# Analog.net
KiCad netlist of a schematic drawn in Altium Designer
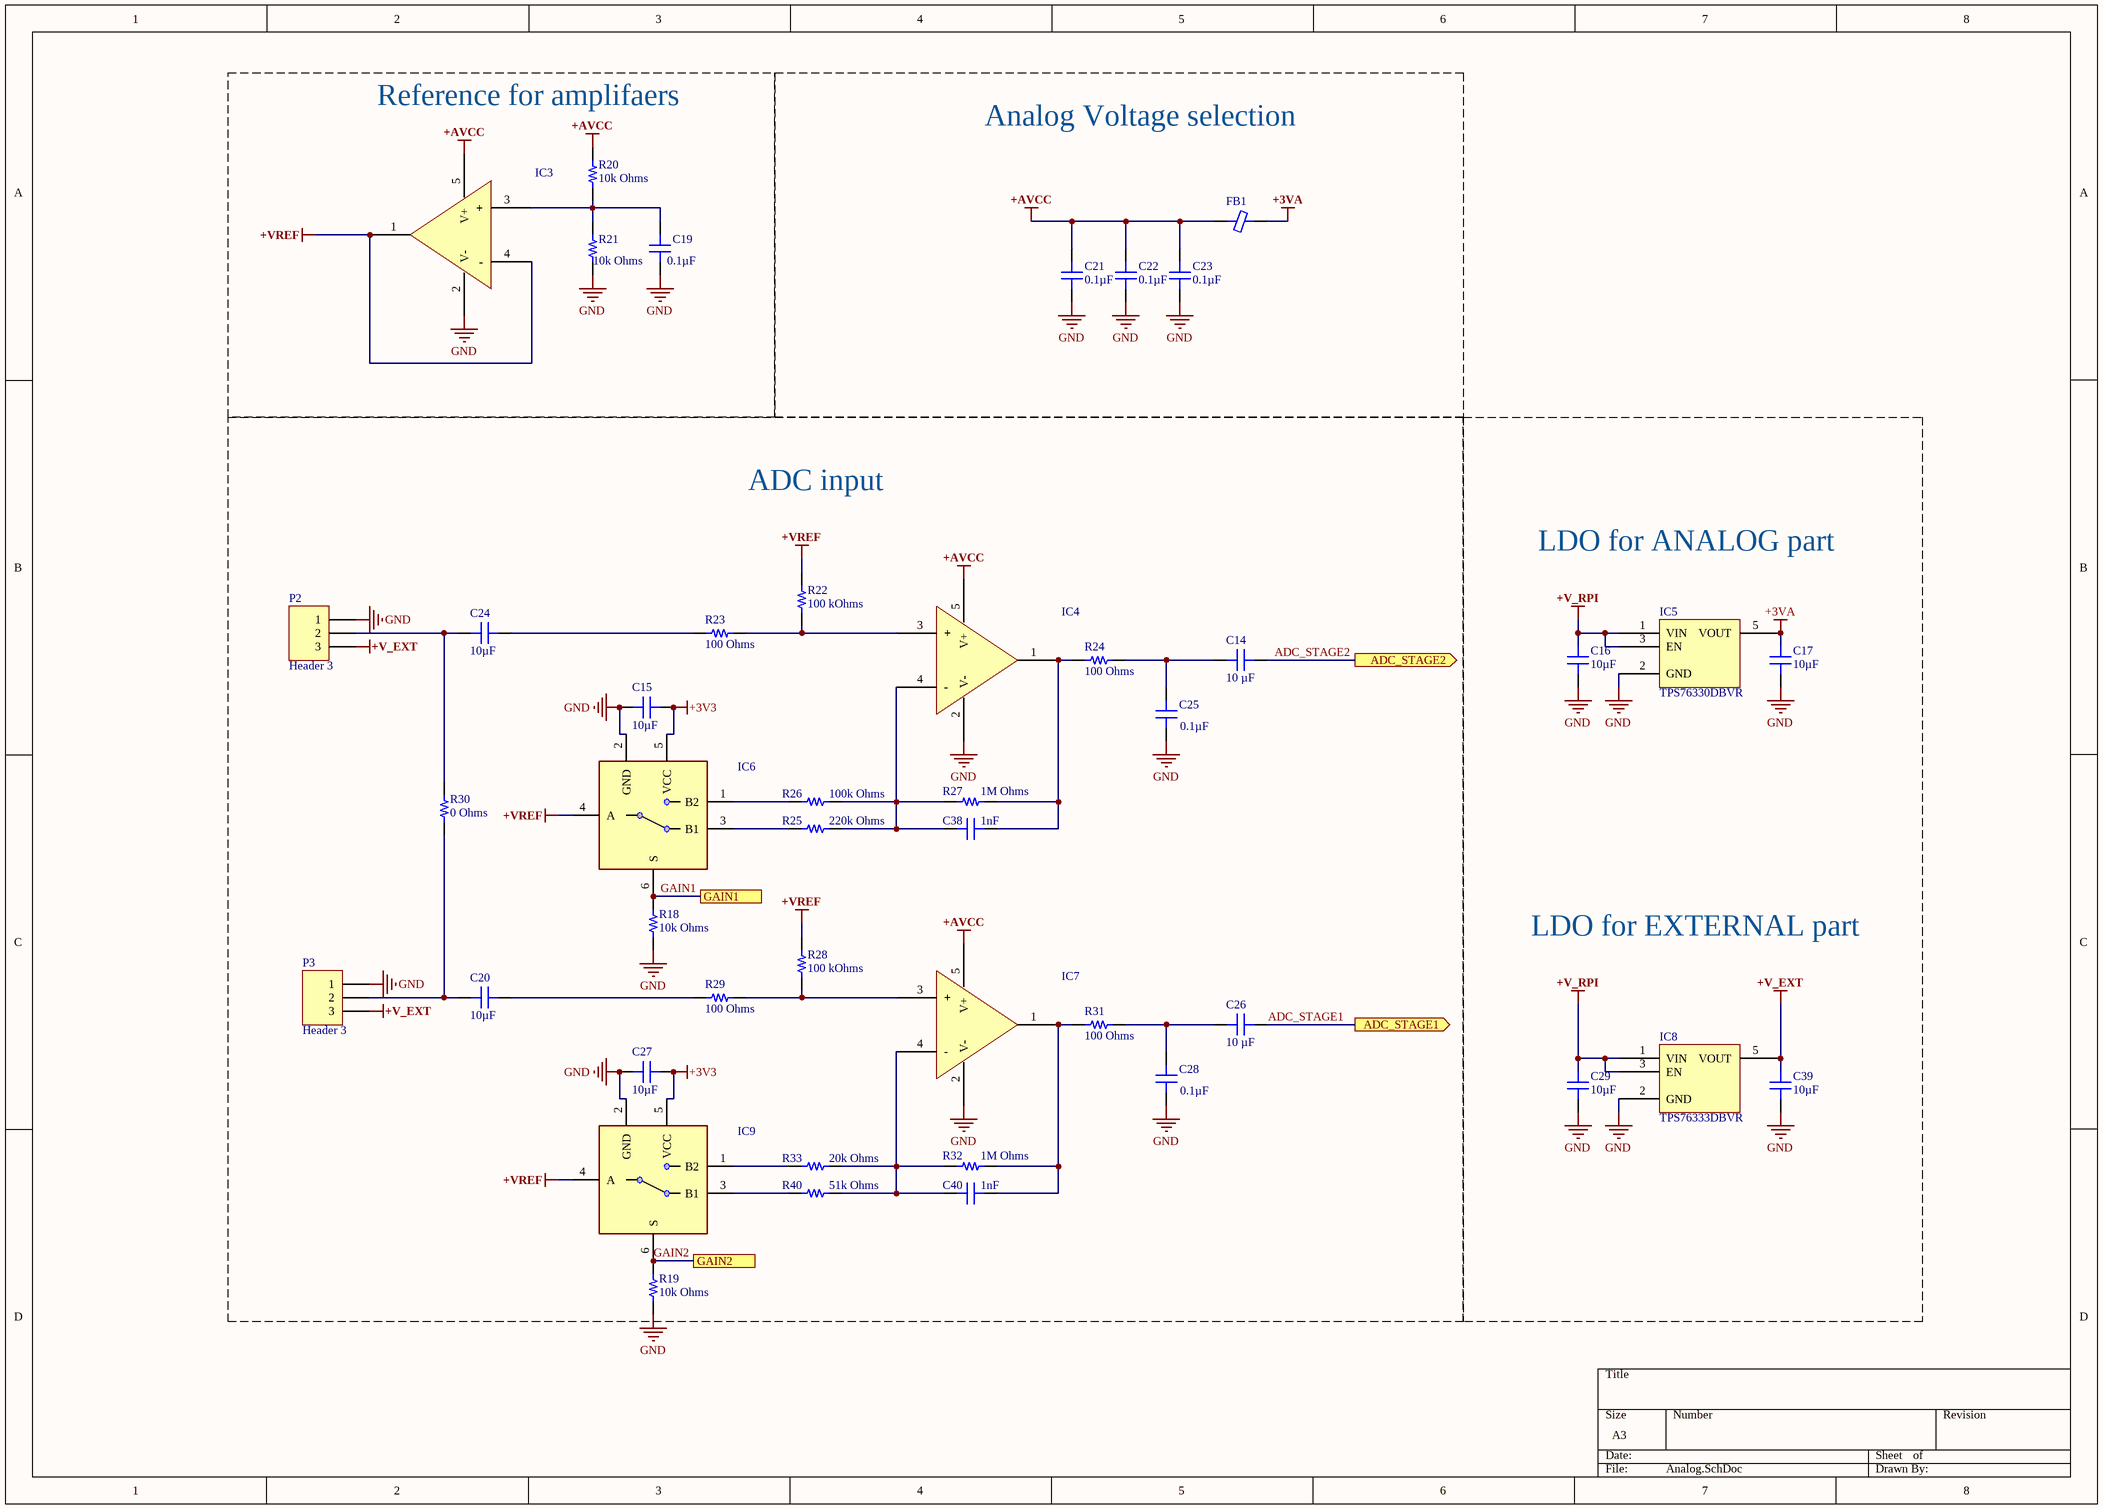
[diagram p0: Analog.SchDoc]

(export (version "E")
  (design (tool "Eeschema 10.0.6"))
  (components
    (comp (ref "C14")
      (value "10 µF")
      (footprint "CAP 0603_1608")
      (description "CAP CER 0.1UF 10V X7R 0603")
      (fields (field (name "PART NUMBER") "100X14W104MV4T"))
      (libsource (lib "Celestial Altium Library - altium_library") (part "Capacitor"))
    )
    (comp (ref "C15")
      (value "10µF")
      (footprint "CAP 0603_1608")
      (description "CAP CER 0.1UF 10V X7R 0603")
      (fields (field (name "PART NUMBER") "100X14W104MV4T"))
      (libsource (lib "Celestial Altium Library - altium_library") (part "Capacitor"))
    )
    (comp (ref "C16")
      (value "10µF")
      (footprint "CAP 0603_1608")
      (description "CAP CER 0.1UF 10V X7R 0603")
      (fields (field (name "PART NUMBER") "100X14W104MV4T"))
      (libsource (lib "Celestial Altium Library - altium_library") (part "Capacitor"))
    )
    (comp (ref "C17")
      (value "10µF")
      (footprint "CAP 0603_1608")
      (description "CAP CER 0.1UF 10V X7R 0603")
      (fields (field (name "PART NUMBER") "100X14W104MV4T"))
      (libsource (lib "Celestial Altium Library - altium_library") (part "Capacitor"))
    )
    (comp (ref "C19")
      (value "0.1µF")
      (footprint "CAP 0603_1608")
      (description "CAP CER 0.1UF 10V X7R 0603")
      (fields (field (name "PART NUMBER") "100X14W104MV4T"))
      (libsource (lib "Celestial Altium Library - altium_library") (part "Capacitor"))
    )
    (comp (ref "C20")
      (value "10µF")
      (footprint "CAP 0603_1608")
      (description "CAP CER 0.1UF 10V X7R 0603")
      (fields (field (name "PART NUMBER") "100X14W104MV4T"))
      (libsource (lib "Celestial Altium Library - altium_library") (part "Capacitor"))
    )
    (comp (ref "C21")
      (value "0.1µF")
      (footprint "CAP 0603_1608")
      (description "CAP CER 0.1UF 10V X7R 0603")
      (fields (field (name "PART NUMBER") "100X14W104MV4T"))
      (libsource (lib "Celestial Altium Library - altium_library") (part "Capacitor"))
    )
    (comp (ref "C22")
      (value "0.1µF")
      (footprint "CAP 0603_1608")
      (description "CAP CER 0.1UF 10V X7R 0603")
      (fields (field (name "PART NUMBER") "100X14W104MV4T"))
      (libsource (lib "Celestial Altium Library - altium_library") (part "Capacitor"))
    )
    (comp (ref "C23")
      (value "0.1µF")
      (footprint "CAP 0603_1608")
      (description "CAP CER 0.1UF 10V X7R 0603")
      (fields (field (name "PART NUMBER") "100X14W104MV4T"))
      (libsource (lib "Celestial Altium Library - altium_library") (part "Capacitor"))
    )
    (comp (ref "C24")
      (value "10µF")
      (footprint "CAP 0603_1608")
      (description "CAP CER 0.1UF 10V X7R 0603")
      (fields (field (name "PART NUMBER") "100X14W104MV4T"))
      (libsource (lib "Celestial Altium Library - altium_library") (part "Capacitor"))
    )
    (comp (ref "C25")
      (value "0.1µF")
      (footprint "CAP 0603_1608")
      (description "CAP CER 0.1UF 10V X7R 0603")
      (fields (field (name "PART NUMBER") "100X14W104MV4T"))
      (libsource (lib "Celestial Altium Library - altium_library") (part "Capacitor"))
    )
    (comp (ref "C26")
      (value "10 µF")
      (footprint "CAP 0603_1608")
      (description "CAP CER 0.1UF 10V X7R 0603")
      (fields (field (name "PART NUMBER") "100X14W104MV4T"))
      (libsource (lib "Celestial Altium Library - altium_library") (part "Capacitor"))
    )
    (comp (ref "C27")
      (value "10µF")
      (footprint "CAP 0603_1608")
      (description "CAP CER 0.1UF 10V X7R 0603")
      (fields (field (name "PART NUMBER") "100X14W104MV4T"))
      (libsource (lib "Celestial Altium Library - altium_library") (part "Capacitor"))
    )
    (comp (ref "C28")
      (value "0.1µF")
      (footprint "CAP 0603_1608")
      (description "CAP CER 0.1UF 10V X7R 0603")
      (fields (field (name "PART NUMBER") "100X14W104MV4T"))
      (libsource (lib "Celestial Altium Library - altium_library") (part "Capacitor"))
    )
    (comp (ref "C29")
      (value "10µF")
      (footprint "CAP 0603_1608")
      (description "CAP CER 0.1UF 10V X7R 0603")
      (fields (field (name "PART NUMBER") "100X14W104MV4T"))
      (libsource (lib "Celestial Altium Library - altium_library") (part "Capacitor"))
    )
    (comp (ref "C38")
      (value "1nF")
      (footprint "CAP 0603_1608")
      (description "CAP CER 0.1UF 10V X7R 0603")
      (fields (field (name "PART NUMBER") "100X14W104MV4T"))
      (libsource (lib "Celestial Altium Library - altium_library") (part "Capacitor"))
    )
    (comp (ref "C39")
      (value "10µF")
      (footprint "CAP 0603_1608")
      (description "CAP CER 0.1UF 10V X7R 0603")
      (fields (field (name "PART NUMBER") "100X14W104MV4T"))
      (libsource (lib "Celestial Altium Library - altium_library") (part "Capacitor"))
    )
    (comp (ref "C40")
      (value "1nF")
      (footprint "CAP 0603_1608")
      (description "CAP CER 0.1UF 10V X7R 0603")
      (fields (field (name "PART NUMBER") "100X14W104MV4T"))
      (libsource (lib "Celestial Altium Library - altium_library") (part "Capacitor"))
    )
    (comp (ref "FB1")
      (value "~")
      (footprint "FER 0603_1608")
      (description "FERRITE BEAD 0603 1LN")
      (fields (field (name "PART NUMBER") "2506031217H0"))
      (libsource (lib "Celestial Altium Library - altium_library") (part "Ferrite Chip"))
    )
    (comp (ref "IC3")
      (value "AD8541ARTZ-REEL7")
      (footprint "ANALOG SOT-23-5 RJ-5")
      (description "IC OPAMP GP 1 CIRCUIT SOT23-5")
      (fields (field (name "MANUFACTURER") "Analog Devices Inc."))
      (libsource (lib "Celestial Altium Library - altium_library") (part "ANALOG DEV AD8541 KS-RJ"))
    )
    (comp (ref "IC4")
      (value "AD8541ARTZ-REEL7")
      (footprint "ANALOG SOT-23-5 RJ-5")
      (description "IC OPAMP GP 1 CIRCUIT SOT23-5")
      (fields (field (name "MANUFACTURER") "Analog Devices Inc."))
      (libsource (lib "Celestial Altium Library - altium_library") (part "ANALOG DEV AD8541 KS-RJ"))
    )
    (comp (ref "IC5")
      (value "TPS76330DBVR")
      (footprint "TI SOT-23-5 DBV")
      (description "IC REG LINEAR 3V 150MA SOT23-5")
      (fields (field (name "MANUFACTURER") "Texas Instruments"))
      (libsource (lib "Celestial Altium Library - altium_library") (part "TI TPS763xx"))
    )
    (comp (ref "IC6")
      (value "SN74LVC1G3157DCK3")
      (footprint "SamacSys:SOT65P210X110-6N")
      (description "Integrated Circuit")
      (fields (field (name "MOUSER PART NUMBER") "595-74LVC1G3157DCK3"))
      (libsource (lib "SamacSys") (part "SN74LVC1G3157DCK3"))
    )
    (comp (ref "IC7")
      (value "AD8541ARTZ-REEL7")
      (footprint "ANALOG SOT-23-5 RJ-5")
      (description "IC OPAMP GP 1 CIRCUIT SOT23-5")
      (fields (field (name "MANUFACTURER") "Analog Devices Inc."))
      (libsource (lib "Celestial Altium Library - altium_library") (part "ANALOG DEV AD8541 KS-RJ"))
    )
    (comp (ref "IC8")
      (value "TPS76333DBVR")
      (footprint "TI SOT-23-5 DBV")
      (description "IC REG LINEAR 3.3V 150MA SOT23-5")
      (libsource (lib "Celestial Altium Library - altium_library") (part "TI TPS763xx"))
    )
    (comp (ref "IC9")
      (value "SN74LVC1G3157DCK3")
      (footprint "SamacSys:SOT65P210X110-6N")
      (description "Integrated Circuit")
      (fields (field (name "MOUSER PART NUMBER") "595-74LVC1G3157DCK3"))
      (libsource (lib "SamacSys") (part "SN74LVC1G3157DCK3"))
    )
    (comp (ref "P2")
      (value "Header 3")
      (footprint "HDR1X3")
      (description "Header, 3-Pin")
      (fields (field (name "PUBLISHER") "Altium Limited"))
      (libsource (lib "Miscellaneous Connectors") (part "Header 3"))
    )
    (comp (ref "P3")
      (value "Header 3")
      (footprint "HDR1X3")
      (description "Header, 3-Pin")
      (fields (field (name "PUBLISHER") "Altium Limited"))
      (libsource (lib "Miscellaneous Connectors") (part "Header 3"))
    )
    (comp (ref "R18")
      (value "10k Ohms")
      (footprint "RES 0603_1608")
      (description "RES 100 OHM 0.1% 1/16W 0603")
      (fields (field (name "PART NUMBER") "RNCS0603BKE100R"))
      (libsource (lib "Celestial Altium Library - altium_library") (part "Resistor"))
    )
    (comp (ref "R19")
      (value "10k Ohms")
      (footprint "RES 0603_1608")
      (description "RES 100 OHM 0.1% 1/16W 0603")
      (fields (field (name "PART NUMBER") "RNCS0603BKE100R"))
      (libsource (lib "Celestial Altium Library - altium_library") (part "Resistor"))
    )
    (comp (ref "R20")
      (value "10k Ohms")
      (footprint "RES 0603_1608")
      (description "RES 100 OHM 0.1% 1/16W 0603")
      (fields (field (name "PART NUMBER") "RNCS0603BKE100R"))
      (libsource (lib "Celestial Altium Library - altium_library") (part "Resistor"))
    )
    (comp (ref "R21")
      (value "10k Ohms")
      (footprint "RES 0603_1608")
      (description "RES 100 OHM 0.1% 1/16W 0603")
      (fields (field (name "PART NUMBER") "RNCS0603BKE100R"))
      (libsource (lib "Celestial Altium Library - altium_library") (part "Resistor"))
    )
    (comp (ref "R22")
      (value "100 kOhms")
      (footprint "RES 0603_1608")
      (description "RES 100 OHM 0.1% 1/16W 0603")
      (fields (field (name "PART NUMBER") "RNCS0603BKE100R"))
      (libsource (lib "Celestial Altium Library - altium_library") (part "Resistor"))
    )
    (comp (ref "R23")
      (value "100 Ohms")
      (footprint "RES 0603_1608")
      (description "RES 100 OHM 0.1% 1/16W 0603")
      (fields (field (name "PART NUMBER") "RNCS0603BKE100R"))
      (libsource (lib "Celestial Altium Library - altium_library") (part "Resistor"))
    )
    (comp (ref "R24")
      (value "100 Ohms")
      (footprint "RES 0603_1608")
      (description "RES 100 OHM 0.1% 1/16W 0603")
      (fields (field (name "PART NUMBER") "RNCS0603BKE100R"))
      (libsource (lib "Celestial Altium Library - altium_library") (part "Resistor"))
    )
    (comp (ref "R25")
      (value "220k Ohms")
      (footprint "RES 0603_1608")
      (description "RES 100 OHM 0.1% 1/16W 0603")
      (fields (field (name "PART NUMBER") "RNCS0603BKE100R"))
      (libsource (lib "Celestial Altium Library - altium_library") (part "Resistor"))
    )
    (comp (ref "R26")
      (value "100k Ohms")
      (footprint "RES 0603_1608")
      (description "RES 100 OHM 0.1% 1/16W 0603")
      (fields (field (name "PART NUMBER") "RNCS0603BKE100R"))
      (libsource (lib "Celestial Altium Library - altium_library") (part "Resistor"))
    )
    (comp (ref "R27")
      (value "1M Ohms")
      (footprint "RES 0603_1608")
      (description "RES 100 OHM 0.1% 1/16W 0603")
      (fields (field (name "PART NUMBER") "RNCS0603BKE100R"))
      (libsource (lib "Celestial Altium Library - altium_library") (part "Resistor"))
    )
    (comp (ref "R28")
      (value "100 kOhms")
      (footprint "RES 0603_1608")
      (description "RES 100 OHM 0.1% 1/16W 0603")
      (fields (field (name "PART NUMBER") "RNCS0603BKE100R"))
      (libsource (lib "Celestial Altium Library - altium_library") (part "Resistor"))
    )
    (comp (ref "R29")
      (value "100 Ohms")
      (footprint "RES 0603_1608")
      (description "RES 100 OHM 0.1% 1/16W 0603")
      (fields (field (name "PART NUMBER") "RNCS0603BKE100R"))
      (libsource (lib "Celestial Altium Library - altium_library") (part "Resistor"))
    )
    (comp (ref "R30")
      (value "0 Ohms")
      (footprint "RES 0603_1608")
      (description "RES 100 OHM 0.1% 1/16W 0603")
      (fields (field (name "PART NUMBER") "RNCS0603BKE100R"))
      (libsource (lib "Celestial Altium Library - altium_library") (part "Resistor"))
    )
    (comp (ref "R31")
      (value "100 Ohms")
      (footprint "RES 0603_1608")
      (description "RES 100 OHM 0.1% 1/16W 0603")
      (fields (field (name "PART NUMBER") "RNCS0603BKE100R"))
      (libsource (lib "Celestial Altium Library - altium_library") (part "Resistor"))
    )
    (comp (ref "R32")
      (value "1M Ohms")
      (footprint "RES 0603_1608")
      (description "RES 100 OHM 0.1% 1/16W 0603")
      (fields (field (name "PART NUMBER") "RNCS0603BKE100R"))
      (libsource (lib "Celestial Altium Library - altium_library") (part "Resistor"))
    )
    (comp (ref "R33")
      (value "20k Ohms")
      (footprint "RES 0603_1608")
      (description "RES 100 OHM 0.1% 1/16W 0603")
      (fields (field (name "PART NUMBER") "RNCS0603BKE100R"))
      (libsource (lib "Celestial Altium Library - altium_library") (part "Resistor"))
    )
    (comp (ref "R40")
      (value "51k Ohms")
      (footprint "RES 0603_1608")
      (description "RES 100 OHM 0.1% 1/16W 0603")
      (fields (field (name "PART NUMBER") "RNCS0603BKE100R"))
      (libsource (lib "Celestial Altium Library - altium_library") (part "Resistor"))
    )
  )
  (nets
    (net (code "1") (name "+3V3") (class "Default")
      (node (ref "C15") (pin "1") (pinfunction "1_1") (pintype "passive"))
      (node (ref "C27") (pin "1") (pinfunction "1_1") (pintype "passive"))
      (node (ref "IC6") (pin "5") (pinfunction "VCC_5") (pintype "passive"))
      (node (ref "IC9") (pin "5") (pinfunction "VCC_5") (pintype "passive"))
    )
    (net (code "2") (name "+3VA") (class "Default")
      (node (ref "C17") (pin "2") (pinfunction "2_2") (pintype "passive"))
      (node (ref "FB1") (pin "2") (pinfunction "2_2") (pintype "passive"))
      (node (ref "IC5") (pin "5") (pinfunction "VOUT_5") (pintype "passive"))
    )
    (net (code "3") (name "+AVCC") (class "Default")
      (node (ref "C21") (pin "2") (pinfunction "2_2") (pintype "passive"))
      (node (ref "C22") (pin "2") (pinfunction "2_2") (pintype "passive"))
      (node (ref "C23") (pin "2") (pinfunction "2_2") (pintype "passive"))
      (node (ref "FB1") (pin "1") (pinfunction "1_1") (pintype "passive"))
      (node (ref "IC3") (pin "5") (pinfunction "V+_5") (pintype "passive"))
      (node (ref "IC4") (pin "5") (pinfunction "V+_5") (pintype "passive"))
      (node (ref "IC7") (pin "5") (pinfunction "V+_5") (pintype "passive"))
      (node (ref "R20") (pin "2") (pinfunction "2_2") (pintype "passive"))
    )
    (net (code "4") (name "+VREF") (class "Default")
      (node (ref "IC3") (pin "1") (pinfunction "OUT_1") (pintype "passive"))
      (node (ref "IC3") (pin "4") (pinfunction "-_4") (pintype "passive"))
      (node (ref "IC6") (pin "4") (pinfunction "A_4") (pintype "passive"))
      (node (ref "IC9") (pin "4") (pinfunction "A_4") (pintype "passive"))
      (node (ref "R22") (pin "1") (pinfunction "1_1") (pintype "passive"))
      (node (ref "R28") (pin "1") (pinfunction "1_1") (pintype "passive"))
    )
    (net (code "5") (name "+V_EXT") (class "Default")
      (node (ref "C39") (pin "2") (pinfunction "2_2") (pintype "passive"))
      (node (ref "IC8") (pin "5") (pinfunction "VOUT_5") (pintype "passive"))
      (node (ref "P2") (pin "3") (pinfunction "3_3") (pintype "passive"))
      (node (ref "P3") (pin "3") (pinfunction "3_3") (pintype "passive"))
    )
    (net (code "6") (name "+V_RPI") (class "Default")
      (node (ref "C16") (pin "2") (pinfunction "2_2") (pintype "passive"))
      (node (ref "C29") (pin "2") (pinfunction "2_2") (pintype "passive"))
      (node (ref "IC5") (pin "1") (pinfunction "VIN_1") (pintype "passive"))
      (node (ref "IC5") (pin "3") (pinfunction "EN_3") (pintype "passive"))
      (node (ref "IC8") (pin "1") (pinfunction "VIN_1") (pintype "passive"))
      (node (ref "IC8") (pin "3") (pinfunction "EN_3") (pintype "passive"))
    )
    (net (code "7") (name "/ADC_STAGE1") (class "Default")
      (node (ref "C26") (pin "2") (pinfunction "2_2") (pintype "passive"))
    )
    (net (code "8") (name "/ADC_STAGE2") (class "Default")
      (node (ref "C14") (pin "2") (pinfunction "2_2") (pintype "passive"))
    )
    (net (code "9") (name "/GAIN1") (class "Default")
      (node (ref "IC6") (pin "6") (pinfunction "S_6") (pintype "passive"))
      (node (ref "R18") (pin "2") (pinfunction "2_2") (pintype "passive"))
    )
    (net (code "10") (name "/GAIN2") (class "Default")
      (node (ref "IC9") (pin "6") (pinfunction "S_6") (pintype "passive"))
      (node (ref "R19") (pin "2") (pinfunction "2_2") (pintype "passive"))
    )
    (net (code "11") (name "GND") (class "Default")
      (node (ref "C15") (pin "2") (pinfunction "2_2") (pintype "passive"))
      (node (ref "C16") (pin "1") (pinfunction "1_1") (pintype "passive"))
      (node (ref "C17") (pin "1") (pinfunction "1_1") (pintype "passive"))
      (node (ref "C19") (pin "1") (pinfunction "1_1") (pintype "passive"))
      (node (ref "C21") (pin "1") (pinfunction "1_1") (pintype "passive"))
      (node (ref "C22") (pin "1") (pinfunction "1_1") (pintype "passive"))
      (node (ref "C23") (pin "1") (pinfunction "1_1") (pintype "passive"))
      (node (ref "C25") (pin "1") (pinfunction "1_1") (pintype "passive"))
      (node (ref "C27") (pin "2") (pinfunction "2_2") (pintype "passive"))
      (node (ref "C28") (pin "1") (pinfunction "1_1") (pintype "passive"))
      (node (ref "C29") (pin "1") (pinfunction "1_1") (pintype "passive"))
      (node (ref "C39") (pin "1") (pinfunction "1_1") (pintype "passive"))
      (node (ref "IC3") (pin "2") (pinfunction "V-_2") (pintype "passive"))
      (node (ref "IC4") (pin "2") (pinfunction "V-_2") (pintype "passive"))
      (node (ref "IC5") (pin "2") (pinfunction "GND_2") (pintype "passive"))
      (node (ref "IC6") (pin "2") (pinfunction "GND_2") (pintype "passive"))
      (node (ref "IC7") (pin "2") (pinfunction "V-_2") (pintype "passive"))
      (node (ref "IC8") (pin "2") (pinfunction "GND_2") (pintype "passive"))
      (node (ref "IC9") (pin "2") (pinfunction "GND_2") (pintype "passive"))
      (node (ref "P2") (pin "1") (pinfunction "1_1") (pintype "passive"))
      (node (ref "P3") (pin "1") (pinfunction "1_1") (pintype "passive"))
      (node (ref "R18") (pin "1") (pinfunction "1_1") (pintype "passive"))
      (node (ref "R19") (pin "1") (pinfunction "1_1") (pintype "passive"))
      (node (ref "R21") (pin "1") (pinfunction "1_1") (pintype "passive"))
    )
    (net (code "12") (name "Net-(C14-Pad1)") (class "Default")
      (node (ref "C14") (pin "1") (pinfunction "1_1") (pintype "passive"))
      (node (ref "C25") (pin "2") (pinfunction "2_2") (pintype "passive"))
      (node (ref "R24") (pin "1") (pinfunction "1_1") (pintype "passive"))
    )
    (net (code "13") (name "Net-(C20-Pad1)") (class "Default")
      (node (ref "C20") (pin "1") (pinfunction "1_1") (pintype "passive"))
      (node (ref "R29") (pin "2") (pinfunction "2_2") (pintype "passive"))
    )
    (net (code "14") (name "Net-(C20-Pad2)") (class "Default")
      (node (ref "C20") (pin "2") (pinfunction "2_2") (pintype "passive"))
      (node (ref "P3") (pin "2") (pinfunction "2_2") (pintype "passive"))
      (node (ref "R30") (pin "2") (pinfunction "2_2") (pintype "passive"))
    )
    (net (code "15") (name "Net-(C24-Pad1)") (class "Default")
      (node (ref "C24") (pin "1") (pinfunction "1_1") (pintype "passive"))
      (node (ref "R23") (pin "2") (pinfunction "2_2") (pintype "passive"))
    )
    (net (code "16") (name "Net-(C24-Pad2)") (class "Default")
      (node (ref "C24") (pin "2") (pinfunction "2_2") (pintype "passive"))
      (node (ref "P2") (pin "2") (pinfunction "2_2") (pintype "passive"))
      (node (ref "R30") (pin "1") (pinfunction "1_1") (pintype "passive"))
    )
    (net (code "17") (name "Net-(C26-Pad1)") (class "Default")
      (node (ref "C26") (pin "1") (pinfunction "1_1") (pintype "passive"))
      (node (ref "C28") (pin "2") (pinfunction "2_2") (pintype "passive"))
      (node (ref "R31") (pin "1") (pinfunction "1_1") (pintype "passive"))
    )
    (net (code "18") (name "Net-(IC3-+)") (class "Default")
      (node (ref "C19") (pin "2") (pinfunction "2_2") (pintype "passive"))
      (node (ref "IC3") (pin "3") (pinfunction "+_3") (pintype "passive"))
      (node (ref "R20") (pin "1") (pinfunction "1_1") (pintype "passive"))
      (node (ref "R21") (pin "2") (pinfunction "2_2") (pintype "passive"))
    )
    (net (code "19") (name "Net-(IC4-+)") (class "Default")
      (node (ref "IC4") (pin "3") (pinfunction "+_3") (pintype "passive"))
      (node (ref "R22") (pin "2") (pinfunction "2_2") (pintype "passive"))
      (node (ref "R23") (pin "1") (pinfunction "1_1") (pintype "passive"))
    )
    (net (code "20") (name "Net-(IC4--)") (class "Default")
      (node (ref "C38") (pin "2") (pinfunction "2_2") (pintype "passive"))
      (node (ref "IC4") (pin "4") (pinfunction "-_4") (pintype "passive"))
      (node (ref "R25") (pin "1") (pinfunction "1_1") (pintype "passive"))
      (node (ref "R26") (pin "1") (pinfunction "1_1") (pintype "passive"))
      (node (ref "R27") (pin "2") (pinfunction "2_2") (pintype "passive"))
    )
    (net (code "21") (name "Net-(IC4-OUT)") (class "Default")
      (node (ref "C38") (pin "1") (pinfunction "1_1") (pintype "passive"))
      (node (ref "IC4") (pin "1") (pinfunction "OUT_1") (pintype "passive"))
      (node (ref "R24") (pin "2") (pinfunction "2_2") (pintype "passive"))
      (node (ref "R27") (pin "1") (pinfunction "1_1") (pintype "passive"))
    )
    (net (code "22") (name "Net-(IC6-B1)") (class "Default")
      (node (ref "IC6") (pin "3") (pinfunction "B1_3") (pintype "passive"))
      (node (ref "R25") (pin "2") (pinfunction "2_2") (pintype "passive"))
    )
    (net (code "23") (name "Net-(IC6-B2)") (class "Default")
      (node (ref "IC6") (pin "1") (pinfunction "B2_1") (pintype "passive"))
      (node (ref "R26") (pin "2") (pinfunction "2_2") (pintype "passive"))
    )
    (net (code "24") (name "Net-(IC7-+)") (class "Default")
      (node (ref "IC7") (pin "3") (pinfunction "+_3") (pintype "passive"))
      (node (ref "R28") (pin "2") (pinfunction "2_2") (pintype "passive"))
      (node (ref "R29") (pin "1") (pinfunction "1_1") (pintype "passive"))
    )
    (net (code "25") (name "Net-(IC7--)") (class "Default")
      (node (ref "C40") (pin "2") (pinfunction "2_2") (pintype "passive"))
      (node (ref "IC7") (pin "4") (pinfunction "-_4") (pintype "passive"))
      (node (ref "R32") (pin "2") (pinfunction "2_2") (pintype "passive"))
      (node (ref "R33") (pin "1") (pinfunction "1_1") (pintype "passive"))
      (node (ref "R40") (pin "1") (pinfunction "1_1") (pintype "passive"))
    )
    (net (code "26") (name "Net-(IC7-OUT)") (class "Default")
      (node (ref "C40") (pin "1") (pinfunction "1_1") (pintype "passive"))
      (node (ref "IC7") (pin "1") (pinfunction "OUT_1") (pintype "passive"))
      (node (ref "R31") (pin "2") (pinfunction "2_2") (pintype "passive"))
      (node (ref "R32") (pin "1") (pinfunction "1_1") (pintype "passive"))
    )
    (net (code "27") (name "Net-(IC9-B1)") (class "Default")
      (node (ref "IC9") (pin "3") (pinfunction "B1_3") (pintype "passive"))
      (node (ref "R40") (pin "2") (pinfunction "2_2") (pintype "passive"))
    )
    (net (code "28") (name "Net-(IC9-B2)") (class "Default")
      (node (ref "IC9") (pin "1") (pinfunction "B2_1") (pintype "passive"))
      (node (ref "R33") (pin "2") (pinfunction "2_2") (pintype "passive"))
    )
  )
)
